# eps_bt2.net
KiCad netlist of a schematic drawn in Altium Designer
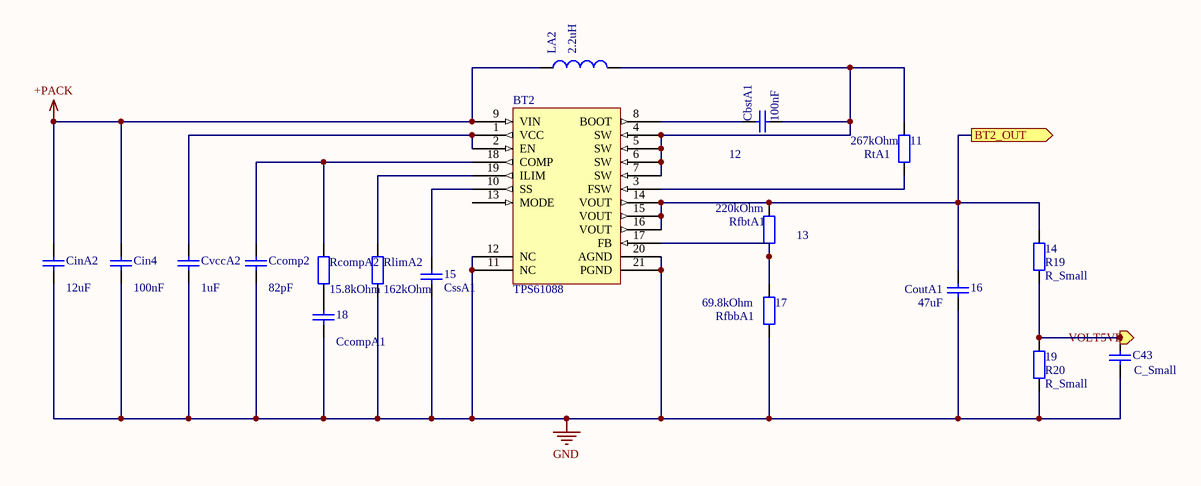
[diagram p0: eps_bt2.SchDoc]

(export (version "E")
  (design (tool "Eeschema 10.0.6"))
  (components
    (comp (ref "11")
      (value "RtA1")
      (footprint "1608[0603]")
      (description "Resistor")
      (fields (field (name "ALTIUM_VALUE") "267kOhm") (field (name "PUBLISHER") "Altium Limited"))
      (libsource (lib "") (part "Res2_1"))
    )
    (comp (ref "12")
      (value "CbstA1")
      (footprint "1608[0603]")
      (description "Capacitor")
      (fields (field (name "ALTIUM_VALUE") "100nF") (field (name "PUBLISHER") "Altium Limited"))
      (libsource (lib "Miscellaneous Devices") (part "Cap"))
    )
    (comp (ref "13")
      (value "RfbtA1")
      (footprint "1608[0603]")
      (description "Resistor")
      (fields (field (name "ALTIUM_VALUE") "220kOhm") (field (name "PUBLISHER") "Altium Limited"))
      (libsource (lib "Miscellaneous Devices") (part "Res2"))
    )
    (comp (ref "14")
      (value "R19")
      (footprint "1608[0603]")
      (description "Resistor")
      (fields (field (name "ALTIUM_VALUE") "R_Small") (field (name "PUBLISHER") "Altium Limited"))
      (libsource (lib "Miscellaneous Devices") (part "Res2"))
    )
    (comp (ref "15")
      (value "CssA1")
      (footprint "1608[0603]")
      (description "Capacitor")
      (fields (field (name "PUBLISHER") "Altium Limited"))
      (libsource (lib "Miscellaneous Devices") (part "Cap"))
    )
    (comp (ref "16")
      (value "CoutA1")
      (footprint "1608[0603]")
      (description "Capacitor")
      (fields (field (name "ALTIUM_VALUE") "47uF") (field (name "PUBLISHER") "Altium Limited"))
      (libsource (lib "Miscellaneous Devices") (part "Cap"))
    )
    (comp (ref "17")
      (value "RfbbA1")
      (footprint "1608[0603]")
      (description "Resistor")
      (fields (field (name "ALTIUM_VALUE") "69.8kOhm") (field (name "PUBLISHER") "Altium Limited"))
      (libsource (lib "Miscellaneous Devices") (part "Res2"))
    )
    (comp (ref "18")
      (value "CcompA1")
      (footprint "1608[0603]")
      (description "Capacitor")
      (fields (field (name "PUBLISHER") "Altium Limited"))
      (libsource (lib "Miscellaneous Devices") (part "Cap"))
    )
    (comp (ref "19")
      (value "R20")
      (footprint "1608[0603]")
      (description "Resistor")
      (fields (field (name "ALTIUM_VALUE") "R_Small") (field (name "PUBLISHER") "Altium Limited"))
      (libsource (lib "Miscellaneous Devices") (part "Res2"))
    )
    (comp (ref "BT2")
      (value "TPS61088")
      (footprint "QFN50P450X350X100-21N")
      (description "Boost converter")
      (libsource (lib "heron-general") (part "TPS61088"))
    )
    (comp (ref "C43")
      (value "C_Small")
      (footprint "1608[0603]")
      (description "Capacitor")
      (fields (field (name "PUBLISHER") "Altium Limited"))
      (libsource (lib "Miscellaneous Devices") (part "Cap"))
    )
    (comp (ref "Ccomp2")
      (value "82pF")
      (footprint "1608[0603]")
      (description "Capacitor")
      (fields (field (name "PUBLISHER") "Altium Limited"))
      (libsource (lib "Miscellaneous Devices") (part "Cap"))
    )
    (comp (ref "Cin4")
      (value "100nF")
      (footprint "1608[0603]")
      (description "Capacitor")
      (fields (field (name "PUBLISHER") "Altium Limited"))
      (libsource (lib "Miscellaneous Devices") (part "Cap"))
    )
    (comp (ref "CinA2")
      (value "12uF")
      (footprint "1608[0603]")
      (description "Capacitor")
      (fields (field (name "PUBLISHER") "Altium Limited"))
      (libsource (lib "Miscellaneous Devices") (part "Cap"))
    )
    (comp (ref "CvccA2")
      (value "1uF")
      (footprint "1608[0603]")
      (description "Capacitor")
      (fields (field (name "PUBLISHER") "Altium Limited"))
      (libsource (lib "Miscellaneous Devices") (part "Cap"))
    )
    (comp (ref "LA2")
      (value "2.2uH")
      (footprint "1608[0603]")
      (description "Inductor")
      (fields (field (name "PUBLISHER") "Altium Limited"))
      (libsource (lib "Miscellaneous Devices") (part "Inductor"))
    )
    (comp (ref "RcompA2")
      (value "15.8kOhm")
      (footprint "1608[0603]")
      (description "Resistor")
      (fields (field (name "PUBLISHER") "Altium Limited"))
      (libsource (lib "Miscellaneous Devices") (part "Res2"))
    )
    (comp (ref "RlimA2")
      (value "162kOhm")
      (footprint "1608[0603]")
      (description "Resistor")
      (fields (field (name "PUBLISHER") "Altium Limited"))
      (libsource (lib "Miscellaneous Devices") (part "Res2"))
    )
  )
  (nets
    (net (code "1") (name "+PACK") (class "Default")
      (node (ref "BT2") (pin "9") (pinfunction "VIN_9") (pintype "input"))
      (node (ref "Cin4") (pin "2") (pinfunction "2_2") (pintype "passive"))
      (node (ref "CinA2") (pin "2") (pinfunction "2_2") (pintype "passive"))
      (node (ref "LA2") (pin "1") (pinfunction "1_1") (pintype "passive"))
    )
    (net (code "2") (name "/BT2_OUT") (class "Default")
      (node (ref "13") (pin "2") (pinfunction "2_2") (pintype "passive"))
      (node (ref "14") (pin "2") (pinfunction "2_2") (pintype "passive"))
      (node (ref "16") (pin "2") (pinfunction "2_2") (pintype "passive"))
      (node (ref "BT2") (pin "14") (pinfunction "VOUT_14") (pintype "output"))
      (node (ref "BT2") (pin "15") (pinfunction "VOUT_15") (pintype "output"))
      (node (ref "BT2") (pin "16") (pinfunction "VOUT_16") (pintype "output"))
    )
    (net (code "3") (name "/VOLT5VB") (class "Default")
      (node (ref "14") (pin "1") (pinfunction "1_1") (pintype "passive"))
      (node (ref "19") (pin "2") (pinfunction "2_2") (pintype "passive"))
      (node (ref "C43") (pin "1") (pinfunction "1_1") (pintype "passive"))
    )
    (net (code "4") (name "GND") (class "Default")
      (node (ref "15") (pin "1") (pinfunction "1_1") (pintype "passive"))
      (node (ref "16") (pin "1") (pinfunction "1_1") (pintype "passive"))
      (node (ref "17") (pin "1") (pinfunction "1_1") (pintype "passive"))
      (node (ref "18") (pin "1") (pinfunction "1_1") (pintype "passive"))
      (node (ref "19") (pin "1") (pinfunction "1_1") (pintype "passive"))
      (node (ref "BT2") (pin "11") (pinfunction "NC_11") (pintype "passive"))
      (node (ref "BT2") (pin "12") (pinfunction "NC_12") (pintype "passive"))
      (node (ref "BT2") (pin "20") (pinfunction "AGND_20") (pintype "power_in"))
      (node (ref "BT2") (pin "21") (pinfunction "PGND_21") (pintype "power_in"))
      (node (ref "C43") (pin "2") (pinfunction "2_2") (pintype "passive"))
      (node (ref "Ccomp2") (pin "1") (pinfunction "1_1") (pintype "passive"))
      (node (ref "Cin4") (pin "1") (pinfunction "1_1") (pintype "passive"))
      (node (ref "CinA2") (pin "1") (pinfunction "1_1") (pintype "passive"))
      (node (ref "CvccA2") (pin "1") (pinfunction "1_1") (pintype "passive"))
      (node (ref "RlimA2") (pin "1") (pinfunction "1_1") (pintype "passive"))
    )
    (net (code "5") (name "Net-(11-Pad1)") (class "Default")
      (node (ref "11") (pin "1") (pinfunction "1_1") (pintype "passive"))
      (node (ref "12") (pin "1") (pinfunction "1_1") (pintype "passive"))
      (node (ref "BT2") (pin "4") (pinfunction "SW_4") (pintype "input"))
      (node (ref "BT2") (pin "5") (pinfunction "SW_5") (pintype "input"))
      (node (ref "BT2") (pin "6") (pinfunction "SW_6") (pintype "input"))
      (node (ref "BT2") (pin "7") (pinfunction "SW_7") (pintype "input"))
      (node (ref "LA2") (pin "2") (pinfunction "2_2") (pintype "passive"))
    )
    (net (code "6") (name "Net-(18-Pad2)") (class "Default")
      (node (ref "18") (pin "2") (pinfunction "2_2") (pintype "passive"))
      (node (ref "RcompA2") (pin "1") (pinfunction "1_1") (pintype "passive"))
    )
    (net (code "7") (name "Net-(BT2-BOOT)") (class "Default")
      (node (ref "12") (pin "2") (pinfunction "2_2") (pintype "passive"))
      (node (ref "BT2") (pin "8") (pinfunction "BOOT_8") (pintype "output"))
    )
    (net (code "8") (name "Net-(BT2-COMP)") (class "Default")
      (node (ref "BT2") (pin "18") (pinfunction "COMP_18") (pintype "output"))
      (node (ref "Ccomp2") (pin "2") (pinfunction "2_2") (pintype "passive"))
      (node (ref "RcompA2") (pin "2") (pinfunction "2_2") (pintype "passive"))
    )
    (net (code "9") (name "Net-(BT2-EN)") (class "Default")
      (node (ref "BT2") (pin "1") (pinfunction "VCC_1") (pintype "output"))
      (node (ref "BT2") (pin "2") (pinfunction "EN_2") (pintype "input"))
      (node (ref "CvccA2") (pin "2") (pinfunction "2_2") (pintype "passive"))
    )
    (net (code "10") (name "Net-(BT2-FB)") (class "Default")
      (node (ref "13") (pin "1") (pinfunction "1_1") (pintype "passive"))
      (node (ref "17") (pin "2") (pinfunction "2_2") (pintype "passive"))
      (node (ref "BT2") (pin "17") (pinfunction "FB_17") (pintype "input"))
    )
    (net (code "11") (name "Net-(BT2-FSW)") (class "Default")
      (node (ref "11") (pin "2") (pinfunction "2_2") (pintype "passive"))
      (node (ref "BT2") (pin "3") (pinfunction "FSW_3") (pintype "input"))
    )
    (net (code "12") (name "Net-(BT2-ILIM)") (class "Default")
      (node (ref "BT2") (pin "19") (pinfunction "ILIM_19") (pintype "output"))
      (node (ref "RlimA2") (pin "2") (pinfunction "2_2") (pintype "passive"))
    )
    (net (code "13") (name "Net-(BT2-SS)") (class "Default")
      (node (ref "15") (pin "2") (pinfunction "2_2") (pintype "passive"))
      (node (ref "BT2") (pin "10") (pinfunction "SS_10") (pintype "output"))
    )
    (net (code "14") (name "unconnected-(BT2-MODE-Pad13)") (class "Default")
      (node (ref "BT2") (pin "13") (pinfunction "MODE_13") (pintype "input"))
    )
  )
)
